# 2_ext_conn.net
KiCad netlist of a schematic drawn in Altium Designer
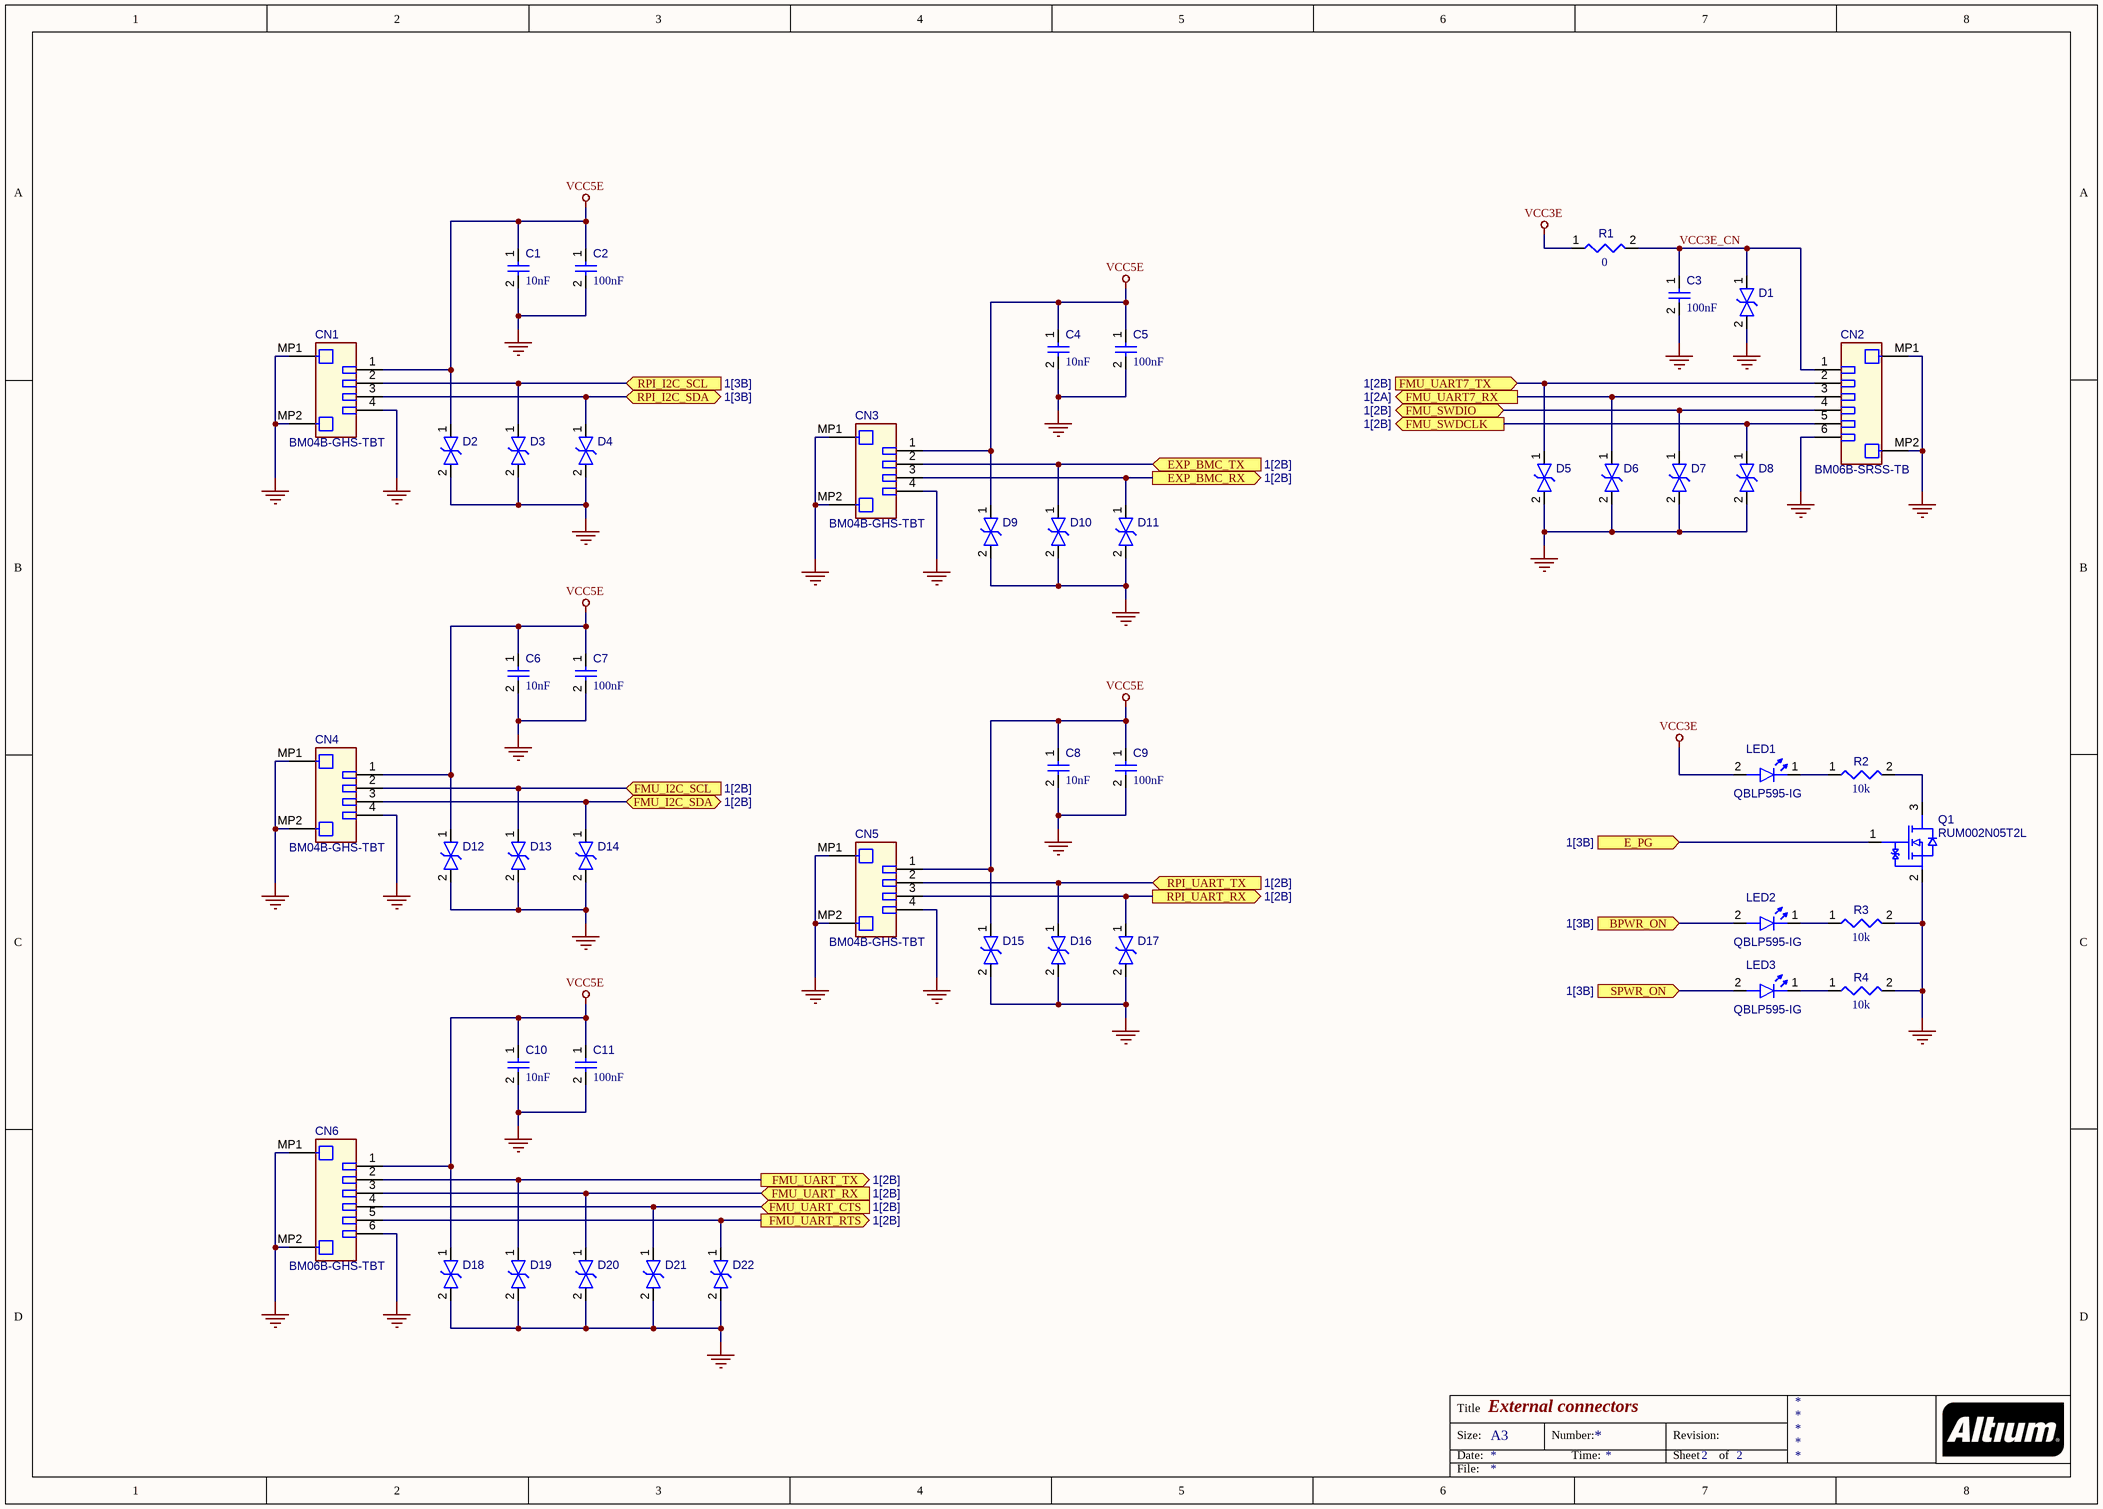
[diagram p0: 2_ext_conn.SchDoc]

(export (version "E")
  (design (tool "Eeschema 10.0.6"))
  (components
    (comp (ref "C1")
      (value "10nF")
      (footprint "CAPC0402(1005)60_L")
      (description "Chip Capacitor, 10nF +/-20%, 50V, 0402, Thickness 0.6 mm")
      (fields (field (name "TOLERANCE") "5%") (field (name "Comment") "Capacitor 10nF +/-20% 50V 0402"))
      (libsource (lib "<Company> Server") (part "CAP-NP-2"))
    )
    (comp (ref "C2")
      (value "100nF")
      (footprint "CAPC0402(1005)60_L")
      (description "Chip Capacitor, 100nF +/-20%, 10V, 0402, Thickness 0.6 mm")
      (fields (field (name "TOLERANCE") "20%") (field (name "Comment") "Capacitor 100nF +/-20% 10V 0402"))
      (libsource (lib "<Company> Server") (part "CAP-NP-2"))
    )
    (comp (ref "C3")
      (value "100nF")
      (footprint "CAPC0402(1005)60_L")
      (description "Chip Capacitor, 100nF +/-20%, 10V, 0402, Thickness 0.6 mm")
      (fields (field (name "TOLERANCE") "20%") (field (name "Comment") "Capacitor 100nF +/-20% 10V 0402"))
      (libsource (lib "<Company> Server") (part "CAP-NP-2"))
    )
    (comp (ref "C4")
      (value "10nF")
      (footprint "CAPC0402(1005)60_L")
      (description "Chip Capacitor, 10nF +/-20%, 50V, 0402, Thickness 0.6 mm")
      (fields (field (name "TOLERANCE") "5%") (field (name "Comment") "Capacitor 10nF +/-20% 50V 0402"))
      (libsource (lib "<Company> Server") (part "CAP-NP-2"))
    )
    (comp (ref "C5")
      (value "100nF")
      (footprint "CAPC0402(1005)60_L")
      (description "Chip Capacitor, 100nF +/-20%, 10V, 0402, Thickness 0.6 mm")
      (fields (field (name "TOLERANCE") "20%") (field (name "Comment") "Capacitor 100nF +/-20% 10V 0402"))
      (libsource (lib "<Company> Server") (part "CAP-NP-2"))
    )
    (comp (ref "C6")
      (value "10nF")
      (footprint "CAPC0402(1005)60_L")
      (description "Chip Capacitor, 10nF +/-20%, 50V, 0402, Thickness 0.6 mm")
      (fields (field (name "TOLERANCE") "5%") (field (name "Comment") "Capacitor 10nF +/-20% 50V 0402"))
      (libsource (lib "<Company> Server") (part "CAP-NP-2"))
    )
    (comp (ref "C7")
      (value "100nF")
      (footprint "CAPC0402(1005)60_L")
      (description "Chip Capacitor, 100nF +/-20%, 10V, 0402, Thickness 0.6 mm")
      (fields (field (name "TOLERANCE") "20%") (field (name "Comment") "Capacitor 100nF +/-20% 10V 0402"))
      (libsource (lib "<Company> Server") (part "CAP-NP-2"))
    )
    (comp (ref "C8")
      (value "10nF")
      (footprint "CAPC0402(1005)60_L")
      (description "Chip Capacitor, 10nF +/-20%, 50V, 0402, Thickness 0.6 mm")
      (fields (field (name "TOLERANCE") "5%") (field (name "Comment") "Capacitor 10nF +/-20% 50V 0402"))
      (libsource (lib "<Company> Server") (part "CAP-NP-2"))
    )
    (comp (ref "C9")
      (value "100nF")
      (footprint "CAPC0402(1005)60_L")
      (description "Chip Capacitor, 100nF +/-20%, 10V, 0402, Thickness 0.6 mm")
      (fields (field (name "TOLERANCE") "20%") (field (name "Comment") "Capacitor 100nF +/-20% 10V 0402"))
      (libsource (lib "<Company> Server") (part "CAP-NP-2"))
    )
    (comp (ref "C10")
      (value "10nF")
      (footprint "CAPC0402(1005)60_L")
      (description "Chip Capacitor, 10nF +/-20%, 50V, 0402, Thickness 0.6 mm")
      (fields (field (name "TOLERANCE") "5%") (field (name "Comment") "Capacitor 10nF +/-20% 50V 0402"))
      (libsource (lib "<Company> Server") (part "CAP-NP-2"))
    )
    (comp (ref "C11")
      (value "100nF")
      (footprint "CAPC0402(1005)60_L")
      (description "Chip Capacitor, 100nF +/-20%, 10V, 0402, Thickness 0.6 mm")
      (fields (field (name "TOLERANCE") "20%") (field (name "Comment") "Capacitor 100nF +/-20% 10V 0402"))
      (libsource (lib "<Company> Server") (part "CAP-NP-2"))
    )
    (comp (ref "CN1")
      (value "BM04B-GHS-TBT")
      (footprint "JST-BM04B-GHS-TBT_V")
      (description "Header, Pitch 1.25 mm, 1 x 4 Position, Height 4.05 mm, -25 to 85 degC")
      (libsource (lib "<Company> Server") (part "CMP-00071-3"))
    )
    (comp (ref "CN2")
      (value "BM06B-SRSS-TB")
      (footprint "JST-BM06B-SRSS-TB_V")
      (description "Header, Pitch 1 mm, 1 x 6 Position, Height 4.25 mm, -25 to 85 degC")
      (libsource (lib "") (part "CMP-00143-5_1"))
    )
    (comp (ref "CN3")
      (value "BM04B-GHS-TBT")
      (footprint "JST-BM04B-GHS-TBT_V")
      (description "Header, Pitch 1.25 mm, 1 x 4 Position, Height 4.05 mm, -25 to 85 degC")
      (libsource (lib "<Company> Server") (part "CMP-00071-3"))
    )
    (comp (ref "CN4")
      (value "BM04B-GHS-TBT")
      (footprint "JST-BM04B-GHS-TBT_V")
      (description "Header, Pitch 1.25 mm, 1 x 4 Position, Height 4.05 mm, -25 to 85 degC")
      (libsource (lib "<Company> Server") (part "CMP-00071-3"))
    )
    (comp (ref "CN5")
      (value "BM04B-GHS-TBT")
      (footprint "JST-BM04B-GHS-TBT_V")
      (description "Header, Pitch 1.25 mm, 1 x 4 Position, Height 4.05 mm, -25 to 85 degC")
      (libsource (lib "<Company> Server") (part "CMP-00071-3"))
    )
    (comp (ref "CN6")
      (value "BM06B-GHS-TBT")
      (footprint "JST-BM06B-GHS-TBT_V")
      (description "Header, Pitch 1.25 mm, 1 x 6 Position, Height 4.05 mm, -25 to 85 degC")
      (libsource (lib "<Company> Server") (part "CMP-00143-5"))
    )
    (comp (ref "D1")
      (value "ESDALC5-1BM2")
      (footprint "STM-SOD-882_V")
      (description "Single Line Low Capacitance Transil™, 5 V, -55 to 150 degC, 2-Pin SOD-882, RoHS, Tape and Reel")
      (libsource (lib "<Company> Server") (part "D-TVS-AA-2"))
    )
    (comp (ref "D2")
      (value "ESDALC5-1BM2")
      (footprint "STM-SOD-882_V")
      (description "Single Line Low Capacitance Transil™, 5 V, -55 to 150 degC, 2-Pin SOD-882, RoHS, Tape and Reel")
      (libsource (lib "<Company> Server") (part "D-TVS-AA-2"))
    )
    (comp (ref "D3")
      (value "ESDALC5-1BM2")
      (footprint "STM-SOD-882_V")
      (description "Single Line Low Capacitance Transil™, 5 V, -55 to 150 degC, 2-Pin SOD-882, RoHS, Tape and Reel")
      (libsource (lib "<Company> Server") (part "D-TVS-AA-2"))
    )
    (comp (ref "D4")
      (value "ESDALC5-1BM2")
      (footprint "STM-SOD-882_V")
      (description "Single Line Low Capacitance Transil™, 5 V, -55 to 150 degC, 2-Pin SOD-882, RoHS, Tape and Reel")
      (libsource (lib "<Company> Server") (part "D-TVS-AA-2"))
    )
    (comp (ref "D5")
      (value "ESDALC5-1BM2")
      (footprint "STM-SOD-882_V")
      (description "Single Line Low Capacitance Transil™, 5 V, -55 to 150 degC, 2-Pin SOD-882, RoHS, Tape and Reel")
      (libsource (lib "<Company> Server") (part "D-TVS-AA-2"))
    )
    (comp (ref "D6")
      (value "ESDALC5-1BM2")
      (footprint "STM-SOD-882_V")
      (description "Single Line Low Capacitance Transil™, 5 V, -55 to 150 degC, 2-Pin SOD-882, RoHS, Tape and Reel")
      (libsource (lib "<Company> Server") (part "D-TVS-AA-2"))
    )
    (comp (ref "D7")
      (value "ESDALC5-1BM2")
      (footprint "STM-SOD-882_V")
      (description "Single Line Low Capacitance Transil™, 5 V, -55 to 150 degC, 2-Pin SOD-882, RoHS, Tape and Reel")
      (libsource (lib "<Company> Server") (part "D-TVS-AA-2"))
    )
    (comp (ref "D8")
      (value "ESDALC5-1BM2")
      (footprint "STM-SOD-882_V")
      (description "Single Line Low Capacitance Transil™, 5 V, -55 to 150 degC, 2-Pin SOD-882, RoHS, Tape and Reel")
      (libsource (lib "<Company> Server") (part "D-TVS-AA-2"))
    )
    (comp (ref "D9")
      (value "ESDALC5-1BM2")
      (footprint "STM-SOD-882_V")
      (description "Single Line Low Capacitance Transil™, 5 V, -55 to 150 degC, 2-Pin SOD-882, RoHS, Tape and Reel")
      (libsource (lib "<Company> Server") (part "D-TVS-AA-2"))
    )
    (comp (ref "D10")
      (value "ESDALC5-1BM2")
      (footprint "STM-SOD-882_V")
      (description "Single Line Low Capacitance Transil™, 5 V, -55 to 150 degC, 2-Pin SOD-882, RoHS, Tape and Reel")
      (libsource (lib "<Company> Server") (part "D-TVS-AA-2"))
    )
    (comp (ref "D11")
      (value "ESDALC5-1BM2")
      (footprint "STM-SOD-882_V")
      (description "Single Line Low Capacitance Transil™, 5 V, -55 to 150 degC, 2-Pin SOD-882, RoHS, Tape and Reel")
      (libsource (lib "<Company> Server") (part "D-TVS-AA-2"))
    )
    (comp (ref "D12")
      (value "ESDALC5-1BM2")
      (footprint "STM-SOD-882_V")
      (description "Single Line Low Capacitance Transil™, 5 V, -55 to 150 degC, 2-Pin SOD-882, RoHS, Tape and Reel")
      (libsource (lib "<Company> Server") (part "D-TVS-AA-2"))
    )
    (comp (ref "D13")
      (value "ESDALC5-1BM2")
      (footprint "STM-SOD-882_V")
      (description "Single Line Low Capacitance Transil™, 5 V, -55 to 150 degC, 2-Pin SOD-882, RoHS, Tape and Reel")
      (libsource (lib "<Company> Server") (part "D-TVS-AA-2"))
    )
    (comp (ref "D14")
      (value "ESDALC5-1BM2")
      (footprint "STM-SOD-882_V")
      (description "Single Line Low Capacitance Transil™, 5 V, -55 to 150 degC, 2-Pin SOD-882, RoHS, Tape and Reel")
      (libsource (lib "<Company> Server") (part "D-TVS-AA-2"))
    )
    (comp (ref "D15")
      (value "ESDALC5-1BM2")
      (footprint "STM-SOD-882_V")
      (description "Single Line Low Capacitance Transil™, 5 V, -55 to 150 degC, 2-Pin SOD-882, RoHS, Tape and Reel")
      (libsource (lib "<Company> Server") (part "D-TVS-AA-2"))
    )
    (comp (ref "D16")
      (value "ESDALC5-1BM2")
      (footprint "STM-SOD-882_V")
      (description "Single Line Low Capacitance Transil™, 5 V, -55 to 150 degC, 2-Pin SOD-882, RoHS, Tape and Reel")
      (libsource (lib "<Company> Server") (part "D-TVS-AA-2"))
    )
    (comp (ref "D17")
      (value "ESDALC5-1BM2")
      (footprint "STM-SOD-882_V")
      (description "Single Line Low Capacitance Transil™, 5 V, -55 to 150 degC, 2-Pin SOD-882, RoHS, Tape and Reel")
      (libsource (lib "<Company> Server") (part "D-TVS-AA-2"))
    )
    (comp (ref "D18")
      (value "ESDALC5-1BM2")
      (footprint "STM-SOD-882_V")
      (description "Single Line Low Capacitance Transil™, 5 V, -55 to 150 degC, 2-Pin SOD-882, RoHS, Tape and Reel")
      (libsource (lib "<Company> Server") (part "D-TVS-AA-2"))
    )
    (comp (ref "D19")
      (value "ESDALC5-1BM2")
      (footprint "STM-SOD-882_V")
      (description "Single Line Low Capacitance Transil™, 5 V, -55 to 150 degC, 2-Pin SOD-882, RoHS, Tape and Reel")
      (libsource (lib "<Company> Server") (part "D-TVS-AA-2"))
    )
    (comp (ref "D20")
      (value "ESDALC5-1BM2")
      (footprint "STM-SOD-882_V")
      (description "Single Line Low Capacitance Transil™, 5 V, -55 to 150 degC, 2-Pin SOD-882, RoHS, Tape and Reel")
      (libsource (lib "<Company> Server") (part "D-TVS-AA-2"))
    )
    (comp (ref "D21")
      (value "ESDALC5-1BM2")
      (footprint "STM-SOD-882_V")
      (description "Single Line Low Capacitance Transil™, 5 V, -55 to 150 degC, 2-Pin SOD-882, RoHS, Tape and Reel")
      (libsource (lib "<Company> Server") (part "D-TVS-AA-2"))
    )
    (comp (ref "D22")
      (value "ESDALC5-1BM2")
      (footprint "STM-SOD-882_V")
      (description "Single Line Low Capacitance Transil™, 5 V, -55 to 150 degC, 2-Pin SOD-882, RoHS, Tape and Reel")
      (libsource (lib "<Company> Server") (part "D-TVS-AA-2"))
    )
    (comp (ref "LED1")
      (value "QBLP595-IG")
      (footprint "QTB-QBLP595_V")
      (description "Chip LED 0402, Green, 0.02 A, 3.1 to 3.7 V, -40 to 80 degC, 2-Pin SMD, RoHS, Tape and Reel")
      (libsource (lib "<Company> Server") (part "LED-KA-2"))
    )
    (comp (ref "LED2")
      (value "QBLP595-IG")
      (footprint "QTB-QBLP595_V")
      (description "Chip LED 0402, Green, 0.02 A, 3.1 to 3.7 V, -40 to 80 degC, 2-Pin SMD, RoHS, Tape and Reel")
      (libsource (lib "<Company> Server") (part "LED-KA-2"))
    )
    (comp (ref "LED3")
      (value "QBLP595-IG")
      (footprint "QTB-QBLP595_V")
      (description "Chip LED 0402, Green, 0.02 A, 3.1 to 3.7 V, -40 to 80 degC, 2-Pin SMD, RoHS, Tape and Reel")
      (libsource (lib "<Company> Server") (part "LED-KA-2"))
    )
    (comp (ref "Q1")
      (value "RUM002N05T2L")
      (footprint "ROHM-SOT723-3_V")
      (description "Nch Small Signal MOSFET, 50 V, 200 mA, 3-Pin SOT723, RoHS, Tape and Reel")
      (libsource (lib "<Company> Server") (part "CMP-00005-6"))
    )
    (comp (ref "R1")
      (value "0")
      (footprint "RESC0603(1608)_L")
      (description "Jumper 0603")
      (libsource (lib "<Company> Server") (part "RES-2"))
    )
    (comp (ref "R2")
      (value "10k")
      (footprint "RESC0402(1005)_L")
      (description "Chip Resistor, 10 kOhms, +/-1 %, 63 mW, -55 to 125 degC, 0402")
      (fields (field (name "TOLERANCE") "1%") (field (name "POWER") "63mW"))
      (libsource (lib "<Company> Server") (part "RES-2"))
    )
    (comp (ref "R3")
      (value "10k")
      (footprint "RESC0402(1005)_L")
      (description "Chip Resistor, 10 kOhms, +/-1 %, 63 mW, -55 to 125 degC, 0402")
      (fields (field (name "TOLERANCE") "1%") (field (name "POWER") "63mW"))
      (libsource (lib "<Company> Server") (part "RES-2"))
    )
    (comp (ref "R4")
      (value "10k")
      (footprint "RESC0402(1005)_L")
      (description "Chip Resistor, 10 kOhms, +/-1 %, 63 mW, -55 to 125 degC, 0402")
      (fields (field (name "TOLERANCE") "1%") (field (name "POWER") "63mW"))
      (libsource (lib "<Company> Server") (part "RES-2"))
    )
  )
  (nets
    (net (code "1") (name "/BPWR_ON") (class "Default")
      (node (ref "LED2") (pin "2") (pinfunction "A_2") (pintype "passive"))
    )
    (net (code "2") (name "/EXP_BMC_RX") (class "Default")
      (node (ref "CN3") (pin "3") (pinfunction "3_3") (pintype "passive"))
      (node (ref "D11") (pin "1") (pinfunction "A_1") (pintype "passive"))
    )
    (net (code "3") (name "/EXP_BMC_TX") (class "Default")
      (node (ref "CN3") (pin "2") (pinfunction "2_2") (pintype "passive"))
      (node (ref "D10") (pin "1") (pinfunction "A_1") (pintype "passive"))
    )
    (net (code "4") (name "/E_PG") (class "Default")
      (node (ref "Q1") (pin "1") (pinfunction "G_1") (pintype "passive"))
    )
    (net (code "5") (name "/FMU_I2C_SCL") (class "Default")
      (node (ref "CN4") (pin "2") (pinfunction "2_2") (pintype "passive"))
      (node (ref "D13") (pin "1") (pinfunction "A_1") (pintype "passive"))
    )
    (net (code "6") (name "/FMU_I2C_SDA") (class "Default")
      (node (ref "CN4") (pin "3") (pinfunction "3_3") (pintype "passive"))
      (node (ref "D14") (pin "1") (pinfunction "A_1") (pintype "passive"))
    )
    (net (code "7") (name "/FMU_SWDCLK") (class "Default")
      (node (ref "CN2") (pin "5") (pinfunction "5_5") (pintype "passive"))
      (node (ref "D8") (pin "1") (pinfunction "A_1") (pintype "passive"))
    )
    (net (code "8") (name "/FMU_SWDIO") (class "Default")
      (node (ref "CN2") (pin "4") (pinfunction "4_4") (pintype "passive"))
      (node (ref "D7") (pin "1") (pinfunction "A_1") (pintype "passive"))
    )
    (net (code "9") (name "/FMU_UART7_RX") (class "Default")
      (node (ref "CN2") (pin "3") (pinfunction "3_3") (pintype "passive"))
      (node (ref "D6") (pin "1") (pinfunction "A_1") (pintype "passive"))
    )
    (net (code "10") (name "/FMU_UART7_TX") (class "Default")
      (node (ref "CN2") (pin "2") (pinfunction "2_2") (pintype "passive"))
      (node (ref "D5") (pin "1") (pinfunction "A_1") (pintype "passive"))
    )
    (net (code "11") (name "/FMU_UART_CTS") (class "Default")
      (node (ref "CN6") (pin "4") (pinfunction "4_4") (pintype "passive"))
      (node (ref "D21") (pin "1") (pinfunction "A_1") (pintype "passive"))
    )
    (net (code "12") (name "/FMU_UART_RTS") (class "Default")
      (node (ref "CN6") (pin "5") (pinfunction "5_5") (pintype "passive"))
      (node (ref "D22") (pin "1") (pinfunction "A_1") (pintype "passive"))
    )
    (net (code "13") (name "/FMU_UART_RX") (class "Default")
      (node (ref "CN6") (pin "3") (pinfunction "3_3") (pintype "passive"))
      (node (ref "D20") (pin "1") (pinfunction "A_1") (pintype "passive"))
    )
    (net (code "14") (name "/FMU_UART_TX") (class "Default")
      (node (ref "CN6") (pin "2") (pinfunction "2_2") (pintype "passive"))
      (node (ref "D19") (pin "1") (pinfunction "A_1") (pintype "passive"))
    )
    (net (code "15") (name "/RPI_I2C_SCL") (class "Default")
      (node (ref "CN1") (pin "2") (pinfunction "2_2") (pintype "passive"))
      (node (ref "D3") (pin "1") (pinfunction "A_1") (pintype "passive"))
    )
    (net (code "16") (name "/RPI_I2C_SDA") (class "Default")
      (node (ref "CN1") (pin "3") (pinfunction "3_3") (pintype "passive"))
      (node (ref "D4") (pin "1") (pinfunction "A_1") (pintype "passive"))
    )
    (net (code "17") (name "/RPI_UART_RX") (class "Default")
      (node (ref "CN5") (pin "3") (pinfunction "3_3") (pintype "passive"))
      (node (ref "D17") (pin "1") (pinfunction "A_1") (pintype "passive"))
    )
    (net (code "18") (name "/RPI_UART_TX") (class "Default")
      (node (ref "CN5") (pin "2") (pinfunction "2_2") (pintype "passive"))
      (node (ref "D16") (pin "1") (pinfunction "A_1") (pintype "passive"))
    )
    (net (code "19") (name "/SPWR_ON") (class "Default")
      (node (ref "LED3") (pin "2") (pinfunction "A_2") (pintype "passive"))
    )
    (net (code "20") (name "/VCC3E_CN") (class "Default")
      (node (ref "C3") (pin "1") (pinfunction "1_1") (pintype "passive"))
      (node (ref "CN2") (pin "1") (pinfunction "1_1") (pintype "passive"))
      (node (ref "D1") (pin "1") (pinfunction "A_1") (pintype "passive"))
      (node (ref "R1") (pin "2") (pinfunction "2_2") (pintype "passive"))
    )
    (net (code "21") (name "GND") (class "Default")
      (node (ref "C1") (pin "2") (pinfunction "2_2") (pintype "passive"))
      (node (ref "C10") (pin "2") (pinfunction "2_2") (pintype "passive"))
      (node (ref "C11") (pin "2") (pinfunction "2_2") (pintype "passive"))
      (node (ref "C2") (pin "2") (pinfunction "2_2") (pintype "passive"))
      (node (ref "C3") (pin "2") (pinfunction "2_2") (pintype "passive"))
      (node (ref "C4") (pin "2") (pinfunction "2_2") (pintype "passive"))
      (node (ref "C5") (pin "2") (pinfunction "2_2") (pintype "passive"))
      (node (ref "C6") (pin "2") (pinfunction "2_2") (pintype "passive"))
      (node (ref "C7") (pin "2") (pinfunction "2_2") (pintype "passive"))
      (node (ref "C8") (pin "2") (pinfunction "2_2") (pintype "passive"))
      (node (ref "C9") (pin "2") (pinfunction "2_2") (pintype "passive"))
      (node (ref "CN1") (pin "4") (pinfunction "4_4") (pintype "passive"))
      (node (ref "CN1") (pin "MP1") (pinfunction "MP1_MP1") (pintype "passive"))
      (node (ref "CN1") (pin "MP2") (pinfunction "MP2_MP2") (pintype "passive"))
      (node (ref "CN2") (pin "6") (pinfunction "6_6") (pintype "passive"))
      (node (ref "CN2") (pin "MP1") (pinfunction "MP1_MP1") (pintype "passive"))
      (node (ref "CN2") (pin "MP2") (pinfunction "MP2_MP2") (pintype "passive"))
      (node (ref "CN3") (pin "4") (pinfunction "4_4") (pintype "passive"))
      (node (ref "CN3") (pin "MP1") (pinfunction "MP1_MP1") (pintype "passive"))
      (node (ref "CN3") (pin "MP2") (pinfunction "MP2_MP2") (pintype "passive"))
      (node (ref "CN4") (pin "4") (pinfunction "4_4") (pintype "passive"))
      (node (ref "CN4") (pin "MP1") (pinfunction "MP1_MP1") (pintype "passive"))
      (node (ref "CN4") (pin "MP2") (pinfunction "MP2_MP2") (pintype "passive"))
      (node (ref "CN5") (pin "4") (pinfunction "4_4") (pintype "passive"))
      (node (ref "CN5") (pin "MP1") (pinfunction "MP1_MP1") (pintype "passive"))
      (node (ref "CN5") (pin "MP2") (pinfunction "MP2_MP2") (pintype "passive"))
      (node (ref "CN6") (pin "6") (pinfunction "6_6") (pintype "passive"))
      (node (ref "CN6") (pin "MP1") (pinfunction "MP1_MP1") (pintype "passive"))
      (node (ref "CN6") (pin "MP2") (pinfunction "MP2_MP2") (pintype "passive"))
      (node (ref "D1") (pin "2") (pinfunction "A_2") (pintype "passive"))
      (node (ref "D10") (pin "2") (pinfunction "A_2") (pintype "passive"))
      (node (ref "D11") (pin "2") (pinfunction "A_2") (pintype "passive"))
      (node (ref "D12") (pin "2") (pinfunction "A_2") (pintype "passive"))
      (node (ref "D13") (pin "2") (pinfunction "A_2") (pintype "passive"))
      (node (ref "D14") (pin "2") (pinfunction "A_2") (pintype "passive"))
      (node (ref "D15") (pin "2") (pinfunction "A_2") (pintype "passive"))
      (node (ref "D16") (pin "2") (pinfunction "A_2") (pintype "passive"))
      (node (ref "D17") (pin "2") (pinfunction "A_2") (pintype "passive"))
      (node (ref "D18") (pin "2") (pinfunction "A_2") (pintype "passive"))
      (node (ref "D19") (pin "2") (pinfunction "A_2") (pintype "passive"))
      (node (ref "D2") (pin "2") (pinfunction "A_2") (pintype "passive"))
      (node (ref "D20") (pin "2") (pinfunction "A_2") (pintype "passive"))
      (node (ref "D21") (pin "2") (pinfunction "A_2") (pintype "passive"))
      (node (ref "D22") (pin "2") (pinfunction "A_2") (pintype "passive"))
      (node (ref "D3") (pin "2") (pinfunction "A_2") (pintype "passive"))
      (node (ref "D4") (pin "2") (pinfunction "A_2") (pintype "passive"))
      (node (ref "D5") (pin "2") (pinfunction "A_2") (pintype "passive"))
      (node (ref "D6") (pin "2") (pinfunction "A_2") (pintype "passive"))
      (node (ref "D7") (pin "2") (pinfunction "A_2") (pintype "passive"))
      (node (ref "D8") (pin "2") (pinfunction "A_2") (pintype "passive"))
      (node (ref "D9") (pin "2") (pinfunction "A_2") (pintype "passive"))
      (node (ref "Q1") (pin "2") (pinfunction "S_2") (pintype "passive"))
      (node (ref "R3") (pin "2") (pinfunction "2_2") (pintype "passive"))
      (node (ref "R4") (pin "2") (pinfunction "2_2") (pintype "passive"))
    )
    (net (code "22") (name "Net-(LED1-K)") (class "Default")
      (node (ref "LED1") (pin "1") (pinfunction "K_1") (pintype "passive"))
      (node (ref "R2") (pin "1") (pinfunction "1_1") (pintype "passive"))
    )
    (net (code "23") (name "Net-(LED2-K)") (class "Default")
      (node (ref "LED2") (pin "1") (pinfunction "K_1") (pintype "passive"))
      (node (ref "R3") (pin "1") (pinfunction "1_1") (pintype "passive"))
    )
    (net (code "24") (name "Net-(LED3-K)") (class "Default")
      (node (ref "LED3") (pin "1") (pinfunction "K_1") (pintype "passive"))
      (node (ref "R4") (pin "1") (pinfunction "1_1") (pintype "passive"))
    )
    (net (code "25") (name "Net-(Q1-D)") (class "Default")
      (node (ref "Q1") (pin "3") (pinfunction "D_3") (pintype "passive"))
      (node (ref "R2") (pin "2") (pinfunction "2_2") (pintype "passive"))
    )
    (net (code "26") (name "VCC3E") (class "Default")
      (node (ref "LED1") (pin "2") (pinfunction "A_2") (pintype "passive"))
      (node (ref "R1") (pin "1") (pinfunction "1_1") (pintype "passive"))
    )
    (net (code "27") (name "VCC5E") (class "Default")
      (node (ref "C1") (pin "1") (pinfunction "1_1") (pintype "passive"))
      (node (ref "C10") (pin "1") (pinfunction "1_1") (pintype "passive"))
      (node (ref "C11") (pin "1") (pinfunction "1_1") (pintype "passive"))
      (node (ref "C2") (pin "1") (pinfunction "1_1") (pintype "passive"))
      (node (ref "C4") (pin "1") (pinfunction "1_1") (pintype "passive"))
      (node (ref "C5") (pin "1") (pinfunction "1_1") (pintype "passive"))
      (node (ref "C6") (pin "1") (pinfunction "1_1") (pintype "passive"))
      (node (ref "C7") (pin "1") (pinfunction "1_1") (pintype "passive"))
      (node (ref "C8") (pin "1") (pinfunction "1_1") (pintype "passive"))
      (node (ref "C9") (pin "1") (pinfunction "1_1") (pintype "passive"))
      (node (ref "CN1") (pin "1") (pinfunction "1_1") (pintype "passive"))
      (node (ref "CN3") (pin "1") (pinfunction "1_1") (pintype "passive"))
      (node (ref "CN4") (pin "1") (pinfunction "1_1") (pintype "passive"))
      (node (ref "CN5") (pin "1") (pinfunction "1_1") (pintype "passive"))
      (node (ref "CN6") (pin "1") (pinfunction "1_1") (pintype "passive"))
      (node (ref "D12") (pin "1") (pinfunction "A_1") (pintype "passive"))
      (node (ref "D15") (pin "1") (pinfunction "A_1") (pintype "passive"))
      (node (ref "D18") (pin "1") (pinfunction "A_1") (pintype "passive"))
      (node (ref "D2") (pin "1") (pinfunction "A_1") (pintype "passive"))
      (node (ref "D9") (pin "1") (pinfunction "A_1") (pintype "passive"))
    )
  )
)
